# MCU.net
KiCad netlist of a schematic drawn in Altium Designer
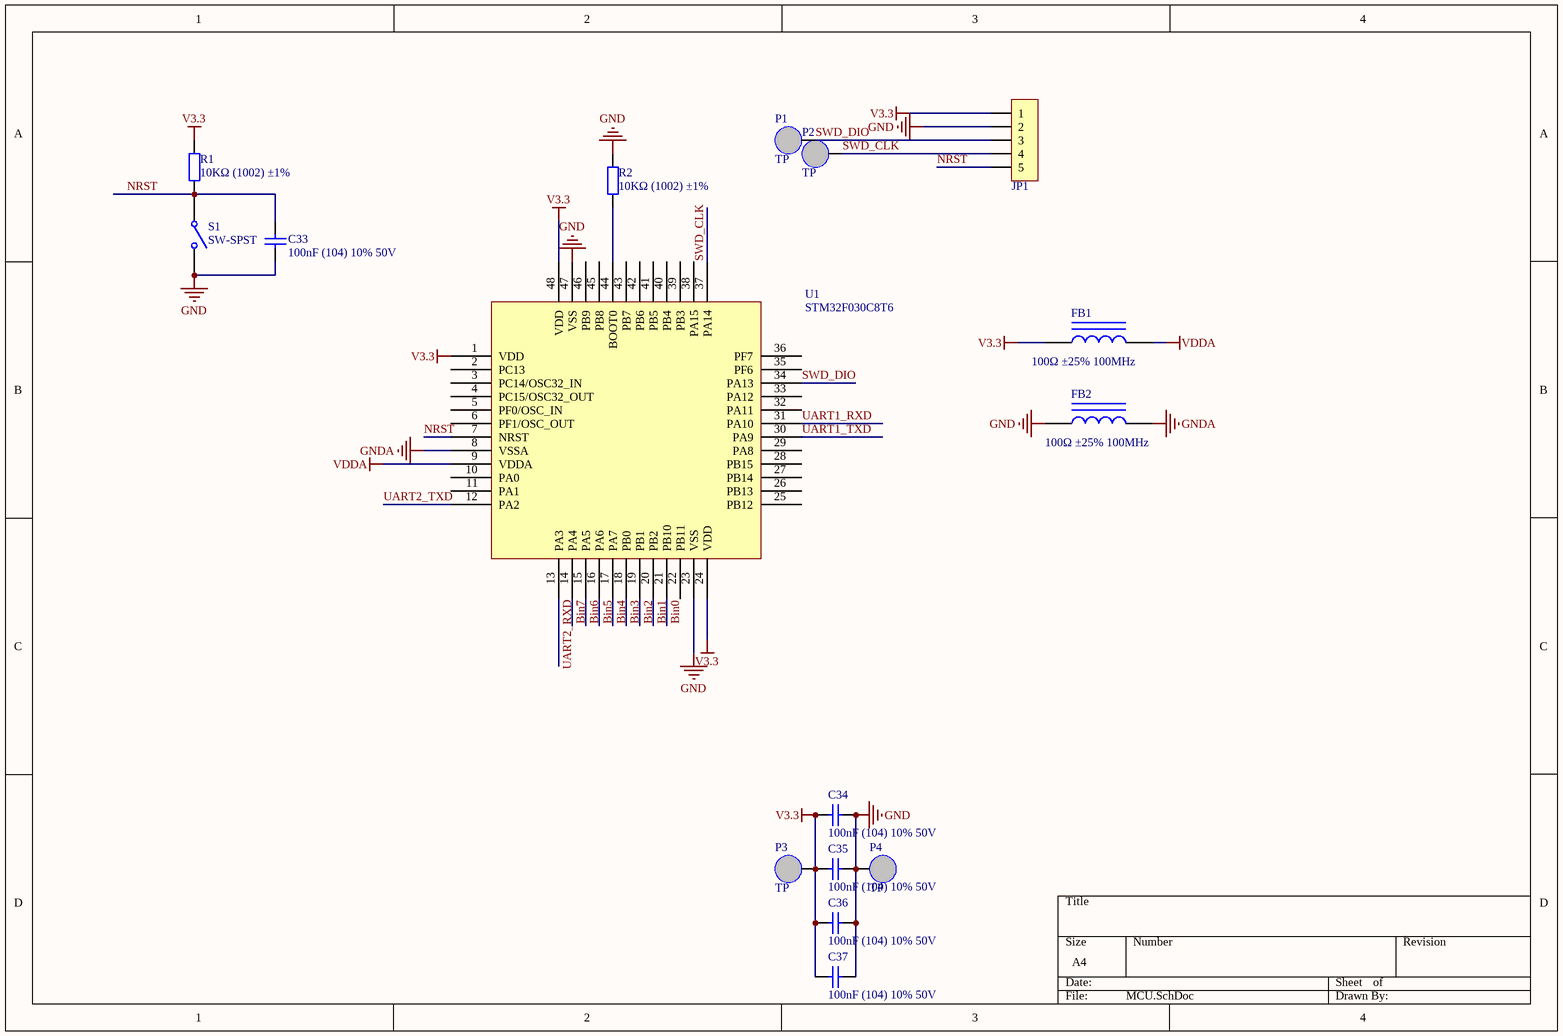
[diagram p0: MCU.SchDoc]

(export (version "E")
  (design (tool "Eeschema 10.0.6"))
  (components
    (comp (ref "C33")
      (value "100nF (104) 10% 50V")
      (footprint "0603_C")
      (description "贴片电容")
      (libsource (lib "Miscellaneous Devices LC") (part "0603 100nF (104) 10% 50V"))
    )
    (comp (ref "C34")
      (value "100nF (104) 10% 50V")
      (footprint "0603_C")
      (description "贴片电容")
      (libsource (lib "Miscellaneous Devices LC") (part "0603 100nF (104) 10% 50V"))
    )
    (comp (ref "C35")
      (value "100nF (104) 10% 50V")
      (footprint "0603_C")
      (description "贴片电容")
      (libsource (lib "Miscellaneous Devices LC") (part "0603 100nF (104) 10% 50V"))
    )
    (comp (ref "C36")
      (value "100nF (104) 10% 50V")
      (footprint "0603_C")
      (description "贴片电容")
      (libsource (lib "Miscellaneous Devices LC") (part "0603 100nF (104) 10% 50V"))
    )
    (comp (ref "C37")
      (value "100nF (104) 10% 50V")
      (footprint "0603_C")
      (description "贴片电容")
      (libsource (lib "Miscellaneous Devices LC") (part "0603 100nF (104) 10% 50V"))
    )
    (comp (ref "FB1")
      (value "100Ω ±25% 100MHz")
      (footprint "0805_L")
      (description "贴片磁珠")
      (libsource (lib "Miscellaneous Devices LC") (part "0805 100Ω 25% 100MHz"))
    )
    (comp (ref "FB2")
      (value "100Ω ±25% 100MHz")
      (footprint "0805_L")
      (description "贴片磁珠")
      (libsource (lib "Miscellaneous Devices LC") (part "0805 100Ω 25% 100MHz"))
    )
    (comp (ref "JP1")
      (value "HDR-1X5")
      (footprint "XH2.54-LI-5P")
      (description "5P接插件")
      (fields (field (name "版权归属") "源创客"))
      (libsource (lib "4.5   - 接插件-脚距2.54") (part "Header 5"))
    )
    (comp (ref "P1") (value "TP") (footprint "TP") (libsource (lib "mylib") (part "TP")))
    (comp (ref "P2") (value "TP") (footprint "TP") (libsource (lib "mylib") (part "TP")))
    (comp (ref "P3") (value "TP") (footprint "TP") (libsource (lib "mylib") (part "TP")))
    (comp (ref "P4") (value "TP") (footprint "TP") (libsource (lib "mylib") (part "TP")))
    (comp (ref "R1")
      (value "10KΩ (1002) ±1%")
      (footprint "0805_R")
      (description "贴片电阻")
      (libsource (lib "Miscellaneous Devices LC") (part "0805 10KΩ (1002) 1%"))
    )
    (comp (ref "R2")
      (value "10KΩ (1002) ±1%")
      (footprint "0603_R")
      (description "贴片电阻")
      (libsource (lib "Miscellaneous Devices LC") (part "0603 10KΩ (1002) 1%"))
    )
    (comp (ref "S1")
      (value "SW-SPST")
      (footprint "TSW SMD-3*6*2.5")
      (description "Single-Pole, Single-Throw Switch")
      (fields (field (name "PUBLISHER") "Altium Limited"))
      (libsource (lib "Miscellaneous Devices") (part "SW-SPST"))
    )
    (comp (ref "U1")
      (value "STM32F030C8T6")
      (footprint "LQFP-48_7x7x05P")
      (description "ARM")
      (libsource (lib "Miscellaneous Devices LC") (part "STM32F030C8T6"))
    )
  )
  (nets
    (net (code "1") (name "/Bin0") (class "Default")
      (node (ref "U1") (pin "21") (pinfunction "PB10_21") (pintype "passive"))
    )
    (net (code "2") (name "/Bin1") (class "Default")
      (node (ref "U1") (pin "20") (pinfunction "PB2_20") (pintype "passive"))
    )
    (net (code "3") (name "/Bin2") (class "Default")
      (node (ref "U1") (pin "19") (pinfunction "PB1_19") (pintype "passive"))
    )
    (net (code "4") (name "/Bin3") (class "Default")
      (node (ref "U1") (pin "18") (pinfunction "PB0_18") (pintype "passive"))
    )
    (net (code "5") (name "/Bin4") (class "Default")
      (node (ref "U1") (pin "17") (pinfunction "PA7_17") (pintype "passive"))
    )
    (net (code "6") (name "/Bin5") (class "Default")
      (node (ref "U1") (pin "16") (pinfunction "PA6_16") (pintype "passive"))
    )
    (net (code "7") (name "/Bin6") (class "Default")
      (node (ref "U1") (pin "15") (pinfunction "PA5_15") (pintype "passive"))
    )
    (net (code "8") (name "/Bin7") (class "Default")
      (node (ref "U1") (pin "14") (pinfunction "PA4_14") (pintype "passive"))
    )
    (net (code "9") (name "/NRST") (class "Default")
      (node (ref "C33") (pin "2") (pinfunction "2_2") (pintype "passive"))
      (node (ref "JP1") (pin "5") (pinfunction "5_5") (pintype "passive"))
      (node (ref "R1") (pin "1") (pinfunction "1_1") (pintype "passive"))
      (node (ref "S1") (pin "1") (pinfunction "COMMON_1") (pintype "passive"))
      (node (ref "U1") (pin "7") (pinfunction "NRST_7") (pintype "passive"))
    )
    (net (code "10") (name "/SWD_CLK") (class "Default")
      (node (ref "JP1") (pin "4") (pinfunction "4_4") (pintype "passive"))
      (node (ref "P2") (pin "1") (pinfunction "1_1") (pintype "passive"))
      (node (ref "U1") (pin "37") (pinfunction "PA14_37") (pintype "passive"))
    )
    (net (code "11") (name "/SWD_DIO") (class "Default")
      (node (ref "JP1") (pin "3") (pinfunction "3_3") (pintype "passive"))
      (node (ref "P1") (pin "1") (pinfunction "1_1") (pintype "passive"))
      (node (ref "U1") (pin "34") (pinfunction "PA13_34") (pintype "passive"))
    )
    (net (code "12") (name "/UART1_RXD") (class "Default")
      (node (ref "U1") (pin "31") (pinfunction "PA10_31") (pintype "passive"))
    )
    (net (code "13") (name "/UART1_TXD") (class "Default")
      (node (ref "U1") (pin "30") (pinfunction "PA9_30") (pintype "passive"))
    )
    (net (code "14") (name "/UART2_RXD") (class "Default")
      (node (ref "U1") (pin "13") (pinfunction "PA3_13") (pintype "passive"))
    )
    (net (code "15") (name "/UART2_TXD") (class "Default")
      (node (ref "U1") (pin "12") (pinfunction "PA2_12") (pintype "passive"))
    )
    (net (code "16") (name "GND") (class "Default")
      (node (ref "C33") (pin "1") (pinfunction "1_1") (pintype "passive"))
      (node (ref "C34") (pin "2") (pinfunction "2_2") (pintype "passive"))
      (node (ref "C35") (pin "2") (pinfunction "2_2") (pintype "passive"))
      (node (ref "C36") (pin "2") (pinfunction "2_2") (pintype "passive"))
      (node (ref "C37") (pin "2") (pinfunction "2_2") (pintype "passive"))
      (node (ref "FB2") (pin "1") (pinfunction "1_1") (pintype "passive"))
      (node (ref "JP1") (pin "2") (pinfunction "2_2") (pintype "passive"))
      (node (ref "P4") (pin "1") (pinfunction "1_1") (pintype "passive"))
      (node (ref "R2") (pin "2") (pinfunction "2_2") (pintype "passive"))
      (node (ref "S1") (pin "2") (pinfunction "NO_2") (pintype "passive"))
      (node (ref "U1") (pin "23") (pinfunction "VSS_23") (pintype "passive"))
      (node (ref "U1") (pin "47") (pinfunction "VSS_47") (pintype "passive"))
    )
    (net (code "17") (name "GNDA") (class "Default")
      (node (ref "FB2") (pin "2") (pinfunction "2_2") (pintype "passive"))
      (node (ref "U1") (pin "8") (pinfunction "VSSA_8") (pintype "passive"))
    )
    (net (code "18") (name "Net-(U1-BOOT0)") (class "Default")
      (node (ref "R2") (pin "1") (pinfunction "1_1") (pintype "passive"))
      (node (ref "U1") (pin "44") (pinfunction "BOOT0_44") (pintype "passive"))
    )
    (net (code "19") (name "V3.3") (class "Default")
      (node (ref "C34") (pin "1") (pinfunction "1_1") (pintype "passive"))
      (node (ref "C35") (pin "1") (pinfunction "1_1") (pintype "passive"))
      (node (ref "C36") (pin "1") (pinfunction "1_1") (pintype "passive"))
      (node (ref "C37") (pin "1") (pinfunction "1_1") (pintype "passive"))
      (node (ref "FB1") (pin "1") (pinfunction "1_1") (pintype "passive"))
      (node (ref "JP1") (pin "1") (pinfunction "1_1") (pintype "passive"))
      (node (ref "P3") (pin "1") (pinfunction "1_1") (pintype "passive"))
      (node (ref "R1") (pin "2") (pinfunction "2_2") (pintype "passive"))
      (node (ref "U1") (pin "1") (pinfunction "VDD_1") (pintype "passive"))
      (node (ref "U1") (pin "24") (pinfunction "VDD_24") (pintype "passive"))
      (node (ref "U1") (pin "48") (pinfunction "VDD_48") (pintype "passive"))
    )
    (net (code "20") (name "VDDA") (class "Default")
      (node (ref "FB1") (pin "2") (pinfunction "2_2") (pintype "passive"))
      (node (ref "U1") (pin "9") (pinfunction "VDDA_9") (pintype "passive"))
    )
    (net (code "21") (name "unconnected-(U1-PA0-Pad10)") (class "Default")
      (node (ref "U1") (pin "10") (pinfunction "PA0_10") (pintype "passive"))
    )
    (net (code "22") (name "unconnected-(U1-PA1-Pad11)") (class "Default")
      (node (ref "U1") (pin "11") (pinfunction "PA1_11") (pintype "passive"))
    )
    (net (code "23") (name "unconnected-(U1-PA8-Pad29)") (class "Default")
      (node (ref "U1") (pin "29") (pinfunction "PA8_29") (pintype "passive"))
    )
    (net (code "24") (name "unconnected-(U1-PA11-Pad32)") (class "Default")
      (node (ref "U1") (pin "32") (pinfunction "PA11_32") (pintype "passive"))
    )
    (net (code "25") (name "unconnected-(U1-PA12-Pad33)") (class "Default")
      (node (ref "U1") (pin "33") (pinfunction "PA12_33") (pintype "passive"))
    )
    (net (code "26") (name "unconnected-(U1-PA15-Pad38)") (class "Default")
      (node (ref "U1") (pin "38") (pinfunction "PA15_38") (pintype "passive"))
    )
    (net (code "27") (name "unconnected-(U1-PB3-Pad39)") (class "Default")
      (node (ref "U1") (pin "39") (pinfunction "PB3_39") (pintype "passive"))
    )
    (net (code "28") (name "unconnected-(U1-PB4-Pad40)") (class "Default")
      (node (ref "U1") (pin "40") (pinfunction "PB4_40") (pintype "passive"))
    )
    (net (code "29") (name "unconnected-(U1-PB5-Pad41)") (class "Default")
      (node (ref "U1") (pin "41") (pinfunction "PB5_41") (pintype "passive"))
    )
    (net (code "30") (name "unconnected-(U1-PB6-Pad42)") (class "Default")
      (node (ref "U1") (pin "42") (pinfunction "PB6_42") (pintype "passive"))
    )
    (net (code "31") (name "unconnected-(U1-PB7-Pad43)") (class "Default")
      (node (ref "U1") (pin "43") (pinfunction "PB7_43") (pintype "passive"))
    )
    (net (code "32") (name "unconnected-(U1-PB8-Pad45)") (class "Default")
      (node (ref "U1") (pin "45") (pinfunction "PB8_45") (pintype "passive"))
    )
    (net (code "33") (name "unconnected-(U1-PB9-Pad46)") (class "Default")
      (node (ref "U1") (pin "46") (pinfunction "PB9_46") (pintype "passive"))
    )
    (net (code "34") (name "unconnected-(U1-PB11-Pad22)") (class "Default")
      (node (ref "U1") (pin "22") (pinfunction "PB11_22") (pintype "passive"))
    )
    (net (code "35") (name "unconnected-(U1-PB12-Pad25)") (class "Default")
      (node (ref "U1") (pin "25") (pinfunction "PB12_25") (pintype "passive"))
    )
    (net (code "36") (name "unconnected-(U1-PB13-Pad26)") (class "Default")
      (node (ref "U1") (pin "26") (pinfunction "PB13_26") (pintype "passive"))
    )
    (net (code "37") (name "unconnected-(U1-PB14-Pad27)") (class "Default")
      (node (ref "U1") (pin "27") (pinfunction "PB14_27") (pintype "passive"))
    )
    (net (code "38") (name "unconnected-(U1-PB15-Pad28)") (class "Default")
      (node (ref "U1") (pin "28") (pinfunction "PB15_28") (pintype "passive"))
    )
    (net (code "39") (name "unconnected-(U1-PC13-Pad2)") (class "Default")
      (node (ref "U1") (pin "2") (pinfunction "PC13_2") (pintype "passive"))
    )
    (net (code "40") (name "unconnected-(U1-PC14{slash}OSC32_IN-Pad3)") (class "Default")
      (node (ref "U1") (pin "3") (pinfunction "PC14/OSC32_IN_3") (pintype "passive"))
    )
    (net (code "41") (name "unconnected-(U1-PC15{slash}OSC32_OUT-Pad4)") (class "Default")
      (node (ref "U1") (pin "4") (pinfunction "PC15/OSC32_OUT_4") (pintype "passive"))
    )
    (net (code "42") (name "unconnected-(U1-PF0{slash}OSC_IN-Pad5)") (class "Default")
      (node (ref "U1") (pin "5") (pinfunction "PF0/OSC_IN_5") (pintype "passive"))
    )
    (net (code "43") (name "unconnected-(U1-PF1{slash}OSC_OUT-Pad6)") (class "Default")
      (node (ref "U1") (pin "6") (pinfunction "PF1/OSC_OUT_6") (pintype "passive"))
    )
    (net (code "44") (name "unconnected-(U1-PF6-Pad35)") (class "Default")
      (node (ref "U1") (pin "35") (pinfunction "PF6_35") (pintype "passive"))
    )
    (net (code "45") (name "unconnected-(U1-PF7-Pad36)") (class "Default")
      (node (ref "U1") (pin "36") (pinfunction "PF7_36") (pintype "passive"))
    )
  )
)
